# PIC24F16KA101.net
KiCad netlist of a schematic drawn in Altium Designer
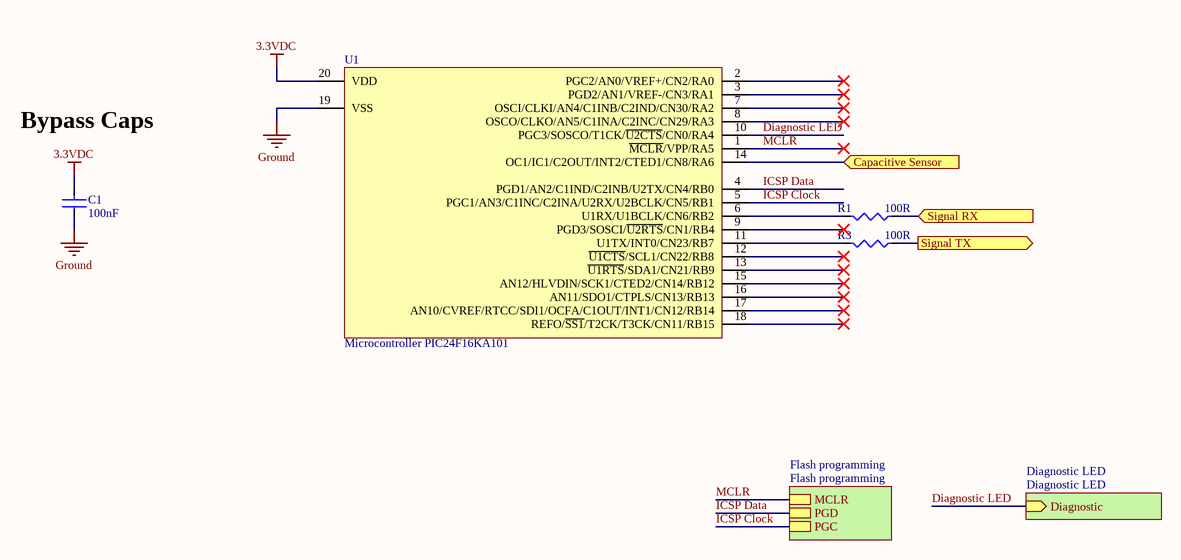
[diagram p0: PIC24F16KA101.SchDoc]

(export (version "E")
  (design (tool "Eeschema 10.0.6"))
  (components
    (comp (ref "C1")
      (value "100nF 0805 100V")
      (footprint "C0805 - Ceramic")
      (fields
        (field (name "MANUFACTURER") "Samsung Electro-Mechanics America, Inc")
        (field (name "MANUFACTURER PART NUMBER") "CL21B104KCFSFNE")
        (field (name "TOLERANCE") "±10%")
        (field (name "CAPACITANCE") "100nF")
      )
      (libsource (lib "Capacitors") (part "100nF 0805 100V"))
    )
    (comp (ref "R1")
      (value "100R 0805 1%")
      (footprint "R0805")
      (description "1/8W")
      (fields
        (field (name "MANUFACTURER") "Stackpole Electronics Inc")
        (field (name "MANUFACTURER PART NUMBER") "RMCF0805FT100R")
        (field (name "RESISTANCE (OHMS)") "100R")
      )
      (libsource (lib "Personal Library") (part "100R 0805 1%"))
    )
    (comp (ref "R3")
      (value "100R 0805 1%")
      (footprint "R0805")
      (description "1/8W")
      (fields
        (field (name "MANUFACTURER") "Stackpole Electronics Inc")
        (field (name "MANUFACTURER PART NUMBER") "RMCF0805FT100R")
        (field (name "RESISTANCE (OHMS)") "100R")
      )
      (libsource (lib "Personal Library") (part "100R 0805 1%"))
    )
    (comp (ref "U1")
      (value "Microcontroller PIC24F16KA101")
      (footprint "SOIC-20")
      (fields
        (field (name "MANUFACTURER") "Microchip Technology")
        (field (name "MANUFACTURER PART NUMBER") "PIC24F16KA101-I/SO")
      )
      (libsource (lib "ICs") (part "Microcontroller PIC24F16KA101"))
    )
  )
  (nets
    (net (code "1") (name "/Capacitive Sensor") (class "Default")
      (node (ref "U1") (pin "14") (pinfunction "OC1/IC1/C2OUT/INT2/CTED1/CN8/RA6_14") (pintype "passive"))
    )
    (net (code "2") (name "/Diagnostic LED") (class "Default")
      (node (ref "U1") (pin "10") (pinfunction "PGC3/SOSCO/T1CK/~{U2CTS}/CN0/RA4_10") (pintype "passive"))
    )
    (net (code "3") (name "/ICSP Clock") (class "Default")
      (node (ref "U1") (pin "5") (pinfunction "PGC1/AN3/C1INC/C2INA/U2RX/U2BCLK/CN5/RB1_5") (pintype "passive"))
    )
    (net (code "4") (name "/ICSP Data") (class "Default")
      (node (ref "U1") (pin "4") (pinfunction "PGD1/AN2/C1IND/C2INB/U2TX/CN4/RB0_4") (pintype "passive"))
    )
    (net (code "5") (name "/MCLR") (class "Default")
      (node (ref "U1") (pin "1") (pinfunction "~{MCLR}/VPP/RA5_1") (pintype "passive+no_connect"))
    )
    (net (code "6") (name "/Signal RX") (class "Default")
      (node (ref "R1") (pin "2") (pinfunction "2_2") (pintype "passive"))
    )
    (net (code "7") (name "/Signal TX") (class "Default")
      (node (ref "R3") (pin "2") (pinfunction "2_2") (pintype "passive"))
    )
    (net (code "8") (name "3.3VDC") (class "Default")
      (node (ref "C1") (pin "1") (pinfunction "1_1") (pintype "passive"))
      (node (ref "U1") (pin "20") (pinfunction "VDD_20") (pintype "passive"))
    )
    (net (code "9") (name "Ground") (class "Default")
      (node (ref "C1") (pin "2") (pinfunction "2_2") (pintype "passive"))
      (node (ref "U1") (pin "19") (pinfunction "VSS_19") (pintype "passive"))
    )
    (net (code "10") (name "Net-(U1-U1RX{slash}U1BCLK{slash}CN6{slash}RB2)") (class "Default")
      (node (ref "R1") (pin "1") (pinfunction "1_1") (pintype "passive"))
      (node (ref "U1") (pin "6") (pinfunction "U1RX/U1BCLK/CN6/RB2_6") (pintype "passive"))
    )
    (net (code "11") (name "Net-(U1-U1TX{slash}INT0{slash}CN23{slash}RB7)") (class "Default")
      (node (ref "R3") (pin "1") (pinfunction "1_1") (pintype "passive"))
      (node (ref "U1") (pin "11") (pinfunction "U1TX/INT0/CN23/RB7_11") (pintype "passive"))
    )
    (net (code "12") (name "unconnected-(U1-AN10{slash}CVREF{slash}RTCC{slash}SDI1{slash}OCFA{slash}C1OUT{slash}INT1{slash}CN12{slash}RB14-Pad17)") (class "Default")
      (node (ref "U1") (pin "17") (pinfunction "AN10/CVREF/RTCC/SDI1/OCFA/C1OUT/INT1/CN12/RB14_17") (pintype "passive+no_connect"))
    )
    (net (code "13") (name "unconnected-(U1-AN11{slash}SDO1{slash}CTPLS{slash}CN13{slash}RB13-Pad16)") (class "Default")
      (node (ref "U1") (pin "16") (pinfunction "AN11/SDO1/CTPLS/CN13/RB13_16") (pintype "passive+no_connect"))
    )
    (net (code "14") (name "unconnected-(U1-AN12{slash}HLVDIN{slash}SCK1{slash}CTED2{slash}CN14{slash}RB12-Pad15)") (class "Default")
      (node (ref "U1") (pin "15") (pinfunction "AN12/HLVDIN/SCK1/CTED2/CN14/RB12_15") (pintype "passive+no_connect"))
    )
    (net (code "15") (name "unconnected-(U1-OSCI{slash}CLKI{slash}AN4{slash}C1INB{slash}C2IND{slash}CN30{slash}RA2-Pad7)") (class "Default")
      (node (ref "U1") (pin "7") (pinfunction "OSCI/CLKI/AN4/C1INB/C2IND/CN30/RA2_7") (pintype "passive+no_connect"))
    )
    (net (code "16") (name "unconnected-(U1-OSCO{slash}CLKO{slash}AN5{slash}C1INA{slash}C2INC{slash}CN29{slash}RA3-Pad8)") (class "Default")
      (node (ref "U1") (pin "8") (pinfunction "OSCO/CLKO/AN5/C1INA/C2INC/CN29/RA3_8") (pintype "passive+no_connect"))
    )
    (net (code "17") (name "unconnected-(U1-PGC2{slash}AN0{slash}VREF+{slash}CN2{slash}RA0-Pad2)") (class "Default")
      (node (ref "U1") (pin "2") (pinfunction "PGC2/AN0/VREF+/CN2/RA0_2") (pintype "passive+no_connect"))
    )
    (net (code "18") (name "unconnected-(U1-PGD2{slash}AN1{slash}VREF-{slash}CN3{slash}RA1-Pad3)") (class "Default")
      (node (ref "U1") (pin "3") (pinfunction "PGD2/AN1/VREF-/CN3/RA1_3") (pintype "passive+no_connect"))
    )
    (net (code "19") (name "unconnected-(U1-PGD3{slash}SOSCI{slash}~{U2RTS}{slash}CN1{slash}RB4-Pad9)") (class "Default")
      (node (ref "U1") (pin "9") (pinfunction "PGD3/SOSCI/~{U2RTS}/CN1/RB4_9") (pintype "passive+no_connect"))
    )
    (net (code "20") (name "unconnected-(U1-REFO{slash}~{SS1}{slash}T2CK{slash}T3CK{slash}CN11{slash}RB15-Pad18)") (class "Default")
      (node (ref "U1") (pin "18") (pinfunction "REFO/~{SS1}/T2CK/T3CK/CN11/RB15_18") (pintype "passive+no_connect"))
    )
    (net (code "21") (name "unconnected-(U1-~{U1CTS}{slash}SCL1{slash}CN22{slash}RB8-Pad12)") (class "Default")
      (node (ref "U1") (pin "12") (pinfunction "~{U1CTS}/SCL1/CN22/RB8_12") (pintype "passive+no_connect"))
    )
    (net (code "22") (name "unconnected-(U1-~{U1RTS}{slash}SDA1{slash}CN21{slash}RB9-Pad13)") (class "Default")
      (node (ref "U1") (pin "13") (pinfunction "~{U1RTS}/SDA1/CN21/RB9_13") (pintype "passive+no_connect"))
    )
  )
)
